# can_transceiver.net
KiCad netlist of a schematic drawn in Altium Designer
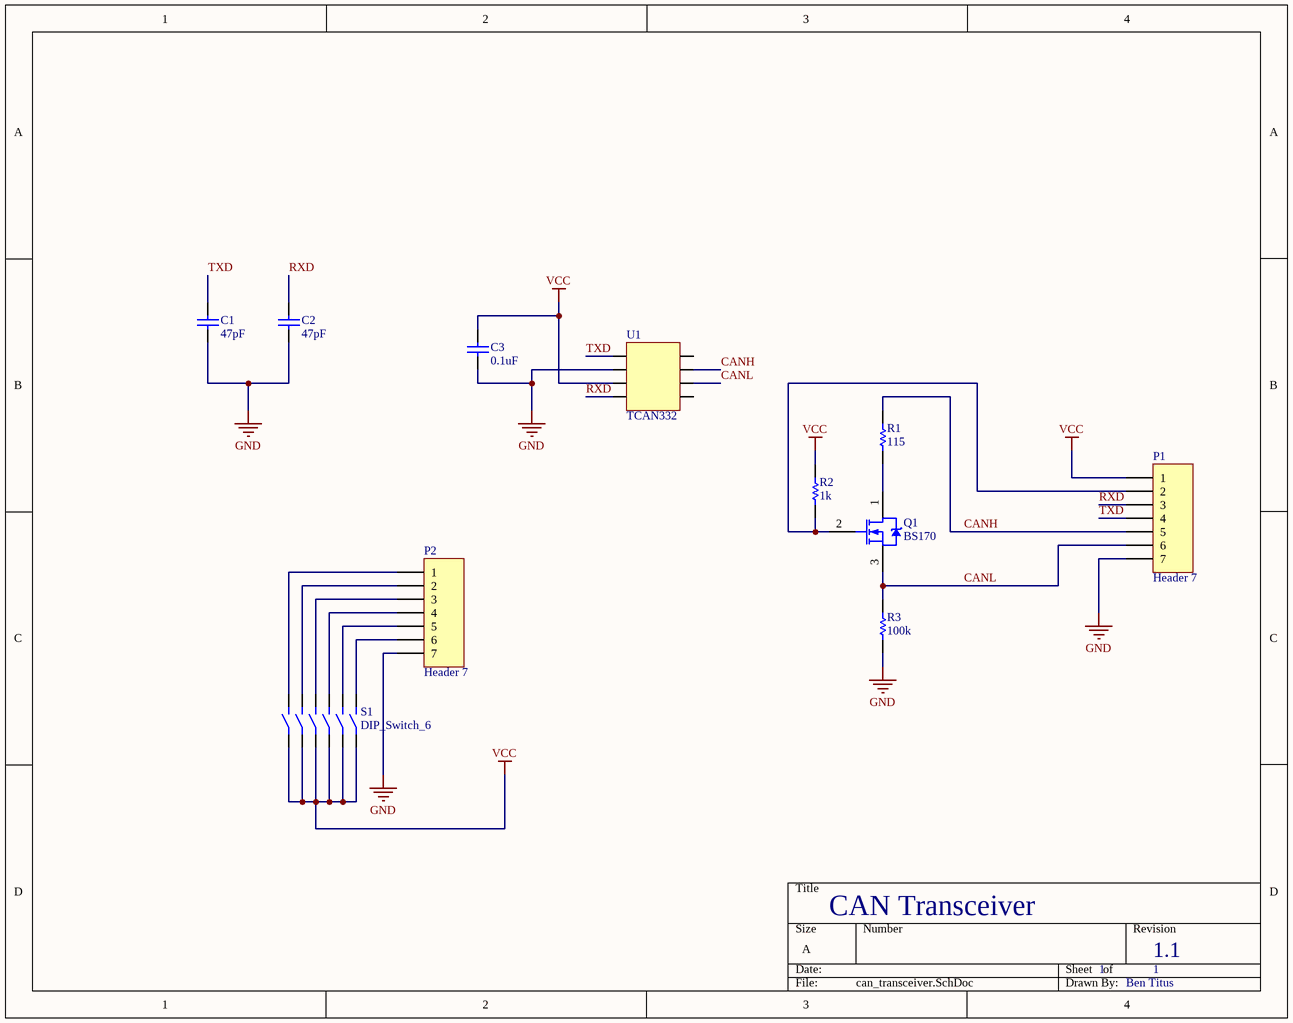
[diagram p0: can_transceiver.SchDoc]

(export (version "E")
  (design (tool "Eeschema 10.0.6"))
  (components
    (comp (ref "C1")
      (value "47pF")
      (footprint "CAPC0805(2012)145_L")
      (description "0805 (2012 Metric) Chip Capacitor")
      (libsource (lib "Altium Content Vault") (part "CAP_5"))
    )
    (comp (ref "C2")
      (value "47pF")
      (footprint "CAPC0805(2012)145_L")
      (description "0805 (2012 Metric) Chip Capacitor")
      (libsource (lib "Altium Content Vault") (part "CAP_5"))
    )
    (comp (ref "C3")
      (value "0.1uF")
      (footprint "CAPC0805(2012)145_L")
      (description "0805 (2012 Metric) Chip Capacitor")
      (libsource (lib "Altium Content Vault") (part "CAP_5"))
    )
    (comp (ref "P1")
      (value "Header 7")
      (footprint "HDR1X7")
      (description "Header, 7-Pin")
      (fields (field (name "PUBLISHER") "Altium Limited"))
      (libsource (lib "Miscellaneous Connectors") (part "Header 7"))
    )
    (comp (ref "P2")
      (value "Header 7")
      (footprint "HDR1X7")
      (description "Header, 7-Pin")
      (fields (field (name "PUBLISHER") "Altium Limited"))
      (libsource (lib "Miscellaneous Connectors") (part "Header 7"))
    )
    (comp (ref "Q1")
      (value "BS170")
      (footprint "ONSC-TO-92-3-29-11")
      (description "Small Signal MOSFET, 500 mA, 60 V, N-Channel, 3-Pin TO-92, Bulk Box")
      (fields (field (name "MANUFACTURER") "On Semiconductor"))
      (libsource (lib "ON Semi MOSFETs") (part "BS170"))
    )
    (comp (ref "R1")
      (value "115")
      (footprint "RESC0805(2012)_L")
      (description "0805 (2012 Metric) Chip Resistor")
      (libsource (lib "Altium Content Vault") (part "RES_3"))
    )
    (comp (ref "R2")
      (value "1k")
      (footprint "RESC0805(2012)_L")
      (description "0805 (2012 Metric) Chip Resistor")
      (libsource (lib "Altium Content Vault") (part "RES_3"))
    )
    (comp (ref "R3")
      (value "100k")
      (footprint "RESC0805(2012)_L")
      (description "0805 (2012 Metric) Chip Resistor")
      (libsource (lib "Altium Content Vault") (part "RES_3"))
    )
    (comp (ref "S1")
      (value "DIP_Switch_6")
      (footprint "SOP12")
      (description "6 pin DIP switch")
      (libsource (lib "Custom_Lib") (part "DIP_Switch_6"))
    )
    (comp (ref "U1")
      (value "TCAN332")
      (footprint "SOP8")
      (description "3.3V CAN Transceiver")
      (libsource (lib "Custom_Lib") (part "TCAN332"))
    )
  )
  (nets
    (net (code "1") (name "/CANH") (class "Default")
      (node (ref "P1") (pin "5") (pinfunction "5_5") (pintype "passive"))
      (node (ref "R1") (pin "2") (pinfunction "2_2") (pintype "passive"))
      (node (ref "U1") (pin "7") (pintype "passive"))
    )
    (net (code "2") (name "/CANL") (class "Default")
      (node (ref "P1") (pin "6") (pinfunction "6_6") (pintype "passive"))
      (node (ref "Q1") (pin "3") (pinfunction "S_3") (pintype "passive"))
      (node (ref "R3") (pin "2") (pinfunction "2_2") (pintype "passive"))
      (node (ref "U1") (pin "6") (pintype "passive"))
    )
    (net (code "3") (name "/RXD") (class "Default")
      (node (ref "C2") (pin "2") (pinfunction "2_2") (pintype "passive"))
      (node (ref "P1") (pin "3") (pinfunction "3_3") (pintype "passive"))
      (node (ref "U1") (pin "4") (pintype "passive"))
    )
    (net (code "4") (name "/TXD") (class "Default")
      (node (ref "C1") (pin "2") (pinfunction "2_2") (pintype "passive"))
      (node (ref "P1") (pin "4") (pinfunction "4_4") (pintype "passive"))
      (node (ref "U1") (pin "1") (pintype "passive"))
    )
    (net (code "5") (name "GND") (class "Default")
      (node (ref "C1") (pin "1") (pinfunction "1_1") (pintype "passive"))
      (node (ref "C2") (pin "1") (pinfunction "1_1") (pintype "passive"))
      (node (ref "C3") (pin "1") (pinfunction "1_1") (pintype "passive"))
      (node (ref "P1") (pin "7") (pinfunction "7_7") (pintype "passive"))
      (node (ref "P2") (pin "7") (pinfunction "7_7") (pintype "passive"))
      (node (ref "R3") (pin "1") (pinfunction "1_1") (pintype "passive"))
      (node (ref "U1") (pin "2") (pintype "passive"))
    )
    (net (code "6") (name "Net-(P2-Pad1)") (class "Default")
      (node (ref "P2") (pin "1") (pinfunction "1_1") (pintype "passive"))
      (node (ref "S1") (pin "12") (pintype "passive"))
    )
    (net (code "7") (name "Net-(P2-Pad2)") (class "Default")
      (node (ref "P2") (pin "2") (pinfunction "2_2") (pintype "passive"))
      (node (ref "S1") (pin "11") (pintype "passive"))
    )
    (net (code "8") (name "Net-(P2-Pad3)") (class "Default")
      (node (ref "P2") (pin "3") (pinfunction "3_3") (pintype "passive"))
      (node (ref "S1") (pin "10") (pintype "passive"))
    )
    (net (code "9") (name "Net-(P2-Pad4)") (class "Default")
      (node (ref "P2") (pin "4") (pinfunction "4_4") (pintype "passive"))
      (node (ref "S1") (pin "9") (pintype "passive"))
    )
    (net (code "10") (name "Net-(P2-Pad5)") (class "Default")
      (node (ref "P2") (pin "5") (pinfunction "5_5") (pintype "passive"))
      (node (ref "S1") (pin "8") (pintype "passive"))
    )
    (net (code "11") (name "Net-(P2-Pad6)") (class "Default")
      (node (ref "P2") (pin "6") (pinfunction "6_6") (pintype "passive"))
      (node (ref "S1") (pin "7") (pintype "passive"))
    )
    (net (code "12") (name "Net-(Q1-D)") (class "Default")
      (node (ref "Q1") (pin "1") (pinfunction "D_1") (pintype "passive"))
      (node (ref "R1") (pin "1") (pinfunction "1_1") (pintype "passive"))
    )
    (net (code "13") (name "Net-(Q1-G)") (class "Default")
      (node (ref "P1") (pin "2") (pinfunction "2_2") (pintype "passive"))
      (node (ref "Q1") (pin "2") (pinfunction "G_2") (pintype "passive"))
      (node (ref "R2") (pin "1") (pinfunction "1_1") (pintype "passive"))
    )
    (net (code "14") (name "VCC") (class "Default")
      (node (ref "C3") (pin "2") (pinfunction "2_2") (pintype "passive"))
      (node (ref "P1") (pin "1") (pinfunction "1_1") (pintype "passive"))
      (node (ref "R2") (pin "2") (pinfunction "2_2") (pintype "passive"))
      (node (ref "S1") (pin "1") (pintype "passive"))
      (node (ref "S1") (pin "2") (pintype "passive"))
      (node (ref "S1") (pin "3") (pintype "passive"))
      (node (ref "S1") (pin "4") (pintype "passive"))
      (node (ref "S1") (pin "5") (pintype "passive"))
      (node (ref "S1") (pin "6") (pintype "passive"))
      (node (ref "U1") (pin "3") (pintype "passive"))
    )
    (net (code "15") (name "unconnected-(U1-Pad5)") (class "Default")
      (node (ref "U1") (pin "5") (pintype "passive"))
    )
    (net (code "16") (name "unconnected-(U1-Pad8)") (class "Default")
      (node (ref "U1") (pin "8") (pintype "passive"))
    )
  )
)
